# MOSFETs.net
KiCad netlist of a schematic drawn in Altium Designer
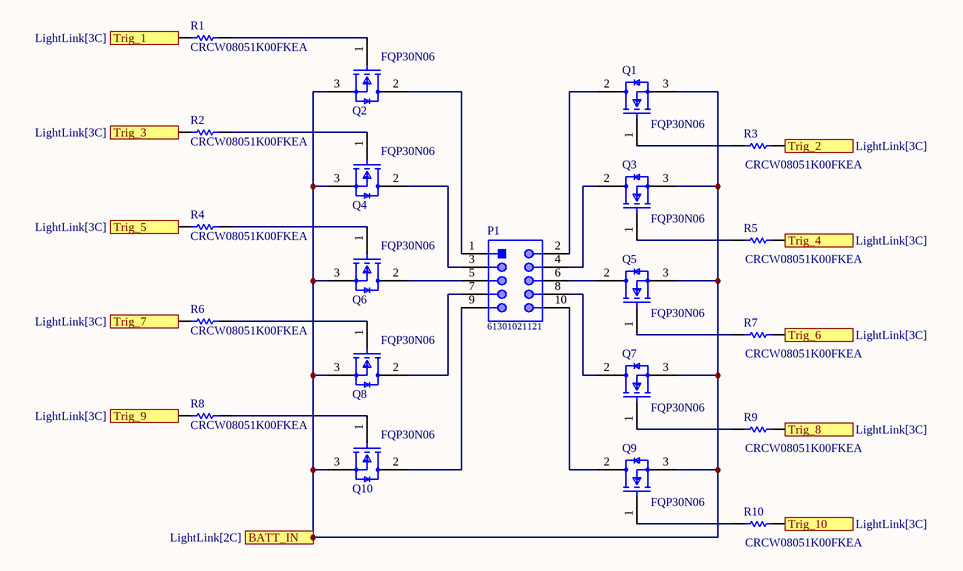
[diagram p0: MOSFETs.SchDoc]

(export (version "E")
  (design (tool "Eeschema 10.0.6"))
  (components
    (comp (ref "P1")
      (value "61301021121")
      (footprint "61301021121")
      (description "THT Vertical Pin Header WR-PHD, Pitch 2.54 mm, Dual Row, 10 pins")
      (fields (field (name "MANUFACTURER") "Wurth Elektronik") (field (name "PUBLISHER") "WurthElektronik"))
      (libsource (lib "Altium Content Vault") (part "WE-CN-2P-M-R10"))
    )
    (comp (ref "Q1")
      (value "FQP30N06")
      (footprint "FP-340AT-MFG")
      (description "MOSFET N-CH 60V 30A TO-220")
      (fields
        (field (name "OCTOPART") "https://octopart.com/fqp30n06-on+semiconductor-84328004")
        (field (name "MANUFACTURER") "ON Semiconductor")
      )
      (libsource (lib "Altium Content Vault") (part "b44c8776e10362b01251f5cff19d373"))
    )
    (comp (ref "Q2")
      (value "FQP30N06")
      (footprint "FP-340AT-MFG")
      (description "MOSFET N-CH 60V 30A TO-220")
      (fields
        (field (name "OCTOPART") "https://octopart.com/fqp30n06-on+semiconductor-84328004")
        (field (name "MANUFACTURER") "ON Semiconductor")
      )
      (libsource (lib "Altium Content Vault") (part "b44c8776e10362b01251f5cff19d373"))
    )
    (comp (ref "Q3")
      (value "FQP30N06")
      (footprint "FP-340AT-MFG")
      (description "MOSFET N-CH 60V 30A TO-220")
      (fields
        (field (name "OCTOPART") "https://octopart.com/fqp30n06-on+semiconductor-84328004")
        (field (name "MANUFACTURER") "ON Semiconductor")
      )
      (libsource (lib "Altium Content Vault") (part "b44c8776e10362b01251f5cff19d373"))
    )
    (comp (ref "Q4")
      (value "FQP30N06")
      (footprint "FP-340AT-MFG")
      (description "MOSFET N-CH 60V 30A TO-220")
      (fields
        (field (name "OCTOPART") "https://octopart.com/fqp30n06-on+semiconductor-84328004")
        (field (name "MANUFACTURER") "ON Semiconductor")
      )
      (libsource (lib "Altium Content Vault") (part "b44c8776e10362b01251f5cff19d373"))
    )
    (comp (ref "Q5")
      (value "FQP30N06")
      (footprint "FP-340AT-MFG")
      (description "MOSFET N-CH 60V 30A TO-220")
      (fields
        (field (name "OCTOPART") "https://octopart.com/fqp30n06-on+semiconductor-84328004")
        (field (name "MANUFACTURER") "ON Semiconductor")
      )
      (libsource (lib "Altium Content Vault") (part "b44c8776e10362b01251f5cff19d373"))
    )
    (comp (ref "Q6")
      (value "FQP30N06")
      (footprint "FP-340AT-MFG")
      (description "MOSFET N-CH 60V 30A TO-220")
      (fields
        (field (name "OCTOPART") "https://octopart.com/fqp30n06-on+semiconductor-84328004")
        (field (name "MANUFACTURER") "ON Semiconductor")
      )
      (libsource (lib "Altium Content Vault") (part "b44c8776e10362b01251f5cff19d373"))
    )
    (comp (ref "Q7")
      (value "FQP30N06")
      (footprint "FP-340AT-MFG")
      (description "MOSFET N-CH 60V 30A TO-220")
      (fields
        (field (name "OCTOPART") "https://octopart.com/fqp30n06-on+semiconductor-84328004")
        (field (name "MANUFACTURER") "ON Semiconductor")
      )
      (libsource (lib "Altium Content Vault") (part "b44c8776e10362b01251f5cff19d373"))
    )
    (comp (ref "Q8")
      (value "FQP30N06")
      (footprint "FP-340AT-MFG")
      (description "MOSFET N-CH 60V 30A TO-220")
      (fields
        (field (name "OCTOPART") "https://octopart.com/fqp30n06-on+semiconductor-84328004")
        (field (name "MANUFACTURER") "ON Semiconductor")
      )
      (libsource (lib "Altium Content Vault") (part "b44c8776e10362b01251f5cff19d373"))
    )
    (comp (ref "Q9")
      (value "FQP30N06")
      (footprint "FP-340AT-MFG")
      (description "MOSFET N-CH 60V 30A TO-220")
      (fields
        (field (name "OCTOPART") "https://octopart.com/fqp30n06-on+semiconductor-84328004")
        (field (name "MANUFACTURER") "ON Semiconductor")
      )
      (libsource (lib "Altium Content Vault") (part "b44c8776e10362b01251f5cff19d373"))
    )
    (comp (ref "Q10")
      (value "FQP30N06")
      (footprint "FP-340AT-MFG")
      (description "MOSFET N-CH 60V 30A TO-220")
      (fields
        (field (name "OCTOPART") "https://octopart.com/fqp30n06-on+semiconductor-84328004")
        (field (name "MANUFACTURER") "ON Semiconductor")
      )
      (libsource (lib "Altium Content Vault") (part "b44c8776e10362b01251f5cff19d373"))
    )
    (comp (ref "R1")
      (value "CRCW08051K00FKEA")
      (footprint "RESC2013X50X30NL20T20")
      (fields (field (name "MANUFACTURER") "Vishay Dale"))
      (libsource (lib "Altium Content Vault") (part "RES"))
    )
    (comp (ref "R2")
      (value "CRCW08051K00FKEA")
      (footprint "RESC2013X50X30NL20T20")
      (fields (field (name "MANUFACTURER") "Vishay Dale"))
      (libsource (lib "Altium Content Vault") (part "RES"))
    )
    (comp (ref "R3")
      (value "CRCW08051K00FKEA")
      (footprint "RESC2013X50X30NL20T20")
      (fields (field (name "MANUFACTURER") "Vishay Dale"))
      (libsource (lib "Altium Content Vault") (part "RES"))
    )
    (comp (ref "R4")
      (value "CRCW08051K00FKEA")
      (footprint "RESC2013X50X30NL20T20")
      (fields (field (name "MANUFACTURER") "Vishay Dale"))
      (libsource (lib "Altium Content Vault") (part "RES"))
    )
    (comp (ref "R5")
      (value "CRCW08051K00FKEA")
      (footprint "RESC2013X50X30NL20T20")
      (fields (field (name "MANUFACTURER") "Vishay Dale"))
      (libsource (lib "Altium Content Vault") (part "RES"))
    )
    (comp (ref "R6")
      (value "CRCW08051K00FKEA")
      (footprint "RESC2013X50X30NL20T20")
      (fields (field (name "MANUFACTURER") "Vishay Dale"))
      (libsource (lib "Altium Content Vault") (part "RES"))
    )
    (comp (ref "R7")
      (value "CRCW08051K00FKEA")
      (footprint "RESC2013X50X30NL20T20")
      (fields (field (name "MANUFACTURER") "Vishay Dale"))
      (libsource (lib "Altium Content Vault") (part "RES"))
    )
    (comp (ref "R8")
      (value "CRCW08051K00FKEA")
      (footprint "RESC2013X50X30NL20T20")
      (fields (field (name "MANUFACTURER") "Vishay Dale"))
      (libsource (lib "Altium Content Vault") (part "RES"))
    )
    (comp (ref "R9")
      (value "CRCW08051K00FKEA")
      (footprint "RESC2013X50X30NL20T20")
      (fields (field (name "MANUFACTURER") "Vishay Dale"))
      (libsource (lib "Altium Content Vault") (part "RES"))
    )
    (comp (ref "R10")
      (value "CRCW08051K00FKEA")
      (footprint "RESC2013X50X30NL20T20")
      (fields (field (name "MANUFACTURER") "Vishay Dale"))
      (libsource (lib "Altium Content Vault") (part "RES"))
    )
  )
  (nets
    (net (code "1") (name "/BATT_IN") (class "Default")
      (node (ref "Q1") (pin "3") (pinfunction "S_3") (pintype "passive"))
      (node (ref "Q10") (pin "3") (pinfunction "S_3") (pintype "passive"))
      (node (ref "Q2") (pin "3") (pinfunction "S_3") (pintype "passive"))
      (node (ref "Q3") (pin "3") (pinfunction "S_3") (pintype "passive"))
      (node (ref "Q4") (pin "3") (pinfunction "S_3") (pintype "passive"))
      (node (ref "Q5") (pin "3") (pinfunction "S_3") (pintype "passive"))
      (node (ref "Q6") (pin "3") (pinfunction "S_3") (pintype "passive"))
      (node (ref "Q7") (pin "3") (pinfunction "S_3") (pintype "passive"))
      (node (ref "Q8") (pin "3") (pinfunction "S_3") (pintype "passive"))
      (node (ref "Q9") (pin "3") (pinfunction "S_3") (pintype "passive"))
    )
    (net (code "2") (name "/Trig_1") (class "Default")
      (node (ref "R1") (pin "1") (pinfunction "1_1") (pintype "passive"))
    )
    (net (code "3") (name "/Trig_2") (class "Default")
      (node (ref "R3") (pin "2") (pinfunction "2_2") (pintype "passive"))
    )
    (net (code "4") (name "/Trig_3") (class "Default")
      (node (ref "R2") (pin "1") (pinfunction "1_1") (pintype "passive"))
    )
    (net (code "5") (name "/Trig_4") (class "Default")
      (node (ref "R5") (pin "2") (pinfunction "2_2") (pintype "passive"))
    )
    (net (code "6") (name "/Trig_5") (class "Default")
      (node (ref "R4") (pin "1") (pinfunction "1_1") (pintype "passive"))
    )
    (net (code "7") (name "/Trig_6") (class "Default")
      (node (ref "R7") (pin "2") (pinfunction "2_2") (pintype "passive"))
    )
    (net (code "8") (name "/Trig_7") (class "Default")
      (node (ref "R6") (pin "1") (pinfunction "1_1") (pintype "passive"))
    )
    (net (code "9") (name "/Trig_8") (class "Default")
      (node (ref "R9") (pin "2") (pinfunction "2_2") (pintype "passive"))
    )
    (net (code "10") (name "/Trig_9") (class "Default")
      (node (ref "R8") (pin "1") (pinfunction "1_1") (pintype "passive"))
    )
    (net (code "11") (name "/Trig_10") (class "Default")
      (node (ref "R10") (pin "2") (pinfunction "2_2") (pintype "passive"))
    )
    (net (code "12") (name "Net-(Q1-D)") (class "Default")
      (node (ref "P1") (pin "2") (pinfunction "2_2") (pintype "passive"))
      (node (ref "Q1") (pin "2") (pinfunction "D_2") (pintype "passive"))
    )
    (net (code "13") (name "Net-(Q1-G)") (class "Default")
      (node (ref "Q1") (pin "1") (pinfunction "G_1") (pintype "passive"))
      (node (ref "R3") (pin "1") (pinfunction "1_1") (pintype "passive"))
    )
    (net (code "14") (name "Net-(Q2-D)") (class "Default")
      (node (ref "P1") (pin "1") (pinfunction "1_1") (pintype "passive"))
      (node (ref "Q2") (pin "2") (pinfunction "D_2") (pintype "passive"))
    )
    (net (code "15") (name "Net-(Q2-G)") (class "Default")
      (node (ref "Q2") (pin "1") (pinfunction "G_1") (pintype "passive"))
      (node (ref "R1") (pin "2") (pinfunction "2_2") (pintype "passive"))
    )
    (net (code "16") (name "Net-(Q3-D)") (class "Default")
      (node (ref "P1") (pin "4") (pinfunction "4_4") (pintype "passive"))
      (node (ref "Q3") (pin "2") (pinfunction "D_2") (pintype "passive"))
    )
    (net (code "17") (name "Net-(Q3-G)") (class "Default")
      (node (ref "Q3") (pin "1") (pinfunction "G_1") (pintype "passive"))
      (node (ref "R5") (pin "1") (pinfunction "1_1") (pintype "passive"))
    )
    (net (code "18") (name "Net-(Q4-D)") (class "Default")
      (node (ref "P1") (pin "3") (pinfunction "3_3") (pintype "passive"))
      (node (ref "Q4") (pin "2") (pinfunction "D_2") (pintype "passive"))
    )
    (net (code "19") (name "Net-(Q4-G)") (class "Default")
      (node (ref "Q4") (pin "1") (pinfunction "G_1") (pintype "passive"))
      (node (ref "R2") (pin "2") (pinfunction "2_2") (pintype "passive"))
    )
    (net (code "20") (name "Net-(Q5-D)") (class "Default")
      (node (ref "P1") (pin "6") (pinfunction "6_6") (pintype "passive"))
      (node (ref "Q5") (pin "2") (pinfunction "D_2") (pintype "passive"))
    )
    (net (code "21") (name "Net-(Q5-G)") (class "Default")
      (node (ref "Q5") (pin "1") (pinfunction "G_1") (pintype "passive"))
      (node (ref "R7") (pin "1") (pinfunction "1_1") (pintype "passive"))
    )
    (net (code "22") (name "Net-(Q6-D)") (class "Default")
      (node (ref "P1") (pin "5") (pinfunction "5_5") (pintype "passive"))
      (node (ref "Q6") (pin "2") (pinfunction "D_2") (pintype "passive"))
    )
    (net (code "23") (name "Net-(Q6-G)") (class "Default")
      (node (ref "Q6") (pin "1") (pinfunction "G_1") (pintype "passive"))
      (node (ref "R4") (pin "2") (pinfunction "2_2") (pintype "passive"))
    )
    (net (code "24") (name "Net-(Q7-D)") (class "Default")
      (node (ref "P1") (pin "8") (pinfunction "8_8") (pintype "passive"))
      (node (ref "Q7") (pin "2") (pinfunction "D_2") (pintype "passive"))
    )
    (net (code "25") (name "Net-(Q7-G)") (class "Default")
      (node (ref "Q7") (pin "1") (pinfunction "G_1") (pintype "passive"))
      (node (ref "R9") (pin "1") (pinfunction "1_1") (pintype "passive"))
    )
    (net (code "26") (name "Net-(Q8-D)") (class "Default")
      (node (ref "P1") (pin "7") (pinfunction "7_7") (pintype "passive"))
      (node (ref "Q8") (pin "2") (pinfunction "D_2") (pintype "passive"))
    )
    (net (code "27") (name "Net-(Q8-G)") (class "Default")
      (node (ref "Q8") (pin "1") (pinfunction "G_1") (pintype "passive"))
      (node (ref "R6") (pin "2") (pinfunction "2_2") (pintype "passive"))
    )
    (net (code "28") (name "Net-(Q9-D)") (class "Default")
      (node (ref "P1") (pin "10") (pinfunction "10_10") (pintype "passive"))
      (node (ref "Q9") (pin "2") (pinfunction "D_2") (pintype "passive"))
    )
    (net (code "29") (name "Net-(Q9-G)") (class "Default")
      (node (ref "Q9") (pin "1") (pinfunction "G_1") (pintype "passive"))
      (node (ref "R10") (pin "1") (pinfunction "1_1") (pintype "passive"))
    )
    (net (code "30") (name "Net-(Q10-D)") (class "Default")
      (node (ref "P1") (pin "9") (pinfunction "9_9") (pintype "passive"))
      (node (ref "Q10") (pin "2") (pinfunction "D_2") (pintype "passive"))
    )
    (net (code "31") (name "Net-(Q10-G)") (class "Default")
      (node (ref "Q10") (pin "1") (pinfunction "G_1") (pintype "passive"))
      (node (ref "R8") (pin "2") (pinfunction "2_2") (pintype "passive"))
    )
  )
)
